# heart_capTouch.net
KiCad netlist of a schematic drawn in EAGLE
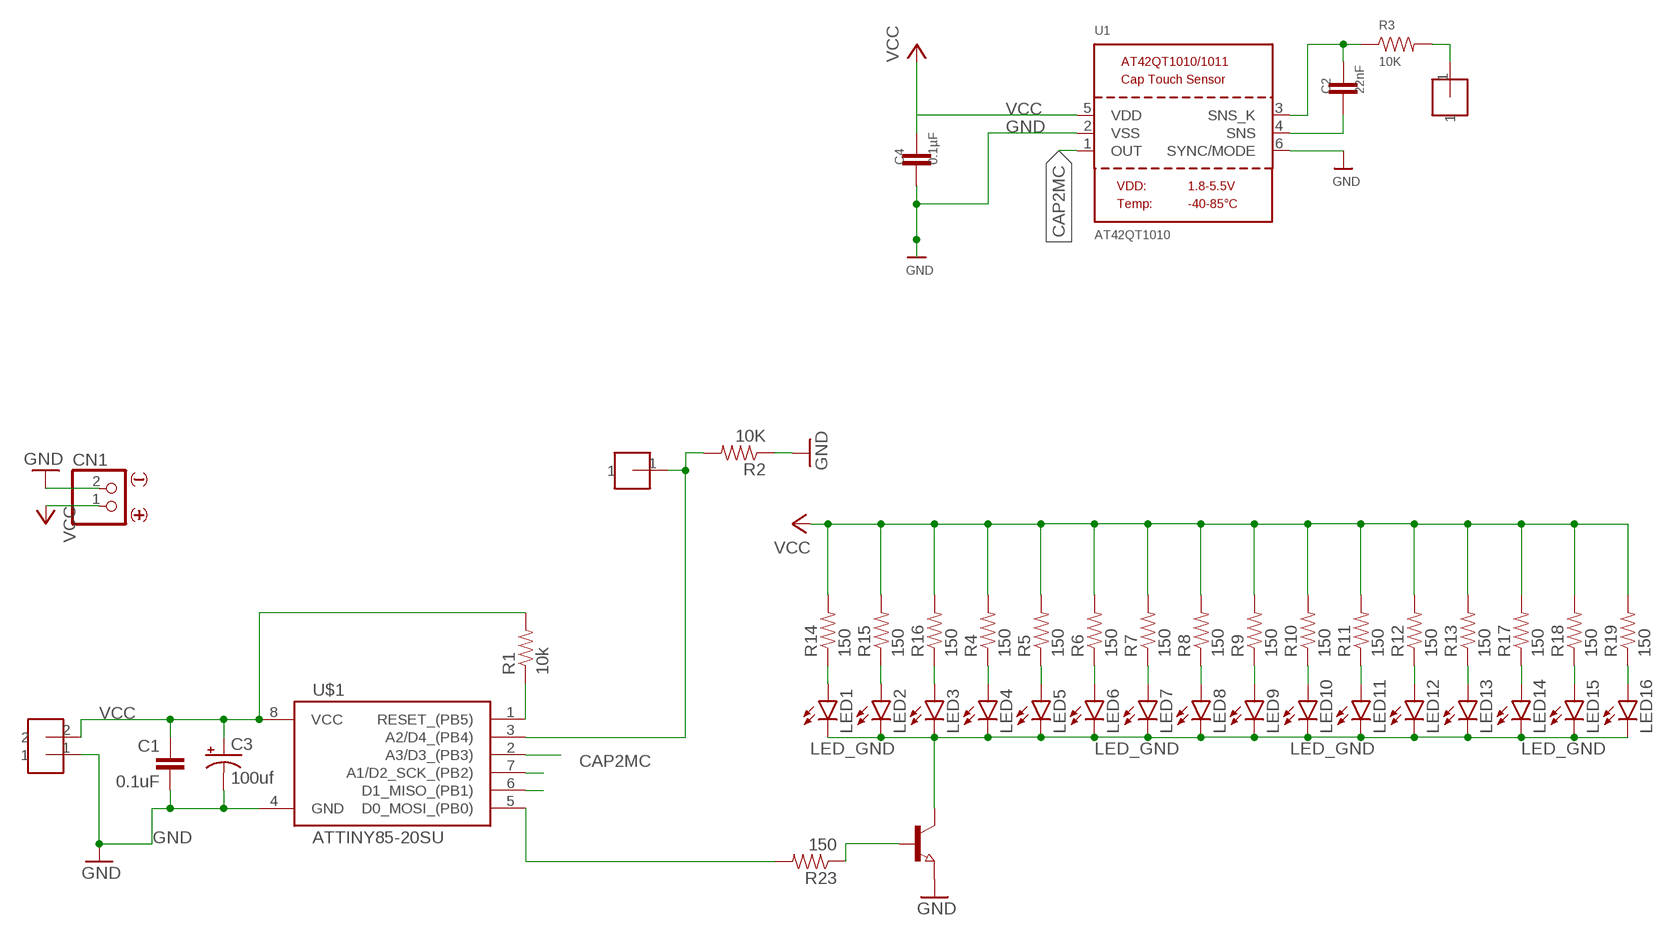
[diagram p0: schematic, sheet 1]

(export (version "E")
  (design (tool "Eeschema 10.0.6"))
  (components
    (comp (ref "C1")
      (value "0.1uF")
      (footprint "eagle-import:0805")
      (libsource (lib "eagle-import") (part "CAP-0805"))
    )
    (comp (ref "C2")
      (value "22nF")
      (footprint "eagle-import:0805")
      (libsource (lib "eagle-import") (part "CAP-0805"))
    )
    (comp (ref "C3")
      (value "100uf")
      (footprint "eagle-import:PANASONIC_D")
      (libsource (lib "eagle-import") (part "CAP_POLD"))
    )
    (comp (ref "C4")
      (value "0.1µF")
      (footprint "eagle-import:0805")
      (libsource (lib "eagle-import") (part "CAP-0805"))
    )
    (comp (ref "CN1")
      (value "JST_2PIN_BATTERY-SMT-HORIZ")
      (footprint "eagle-import:JST-PH-2-SMT-RA")
      (libsource (lib "eagle-import") (part "JST_2PIN_BATTERY-SMT-HORIZ"))
    )
    (comp (ref "LED1")
      (value "LED0603")
      (footprint "eagle-import:LED-0603")
      (libsource (lib "eagle-import") (part "LED0603"))
    )
    (comp (ref "LED2")
      (value "LED0603")
      (footprint "eagle-import:LED-0603")
      (libsource (lib "eagle-import") (part "LED0603"))
    )
    (comp (ref "LED3")
      (value "LED0603")
      (footprint "eagle-import:LED-0603")
      (libsource (lib "eagle-import") (part "LED0603"))
    )
    (comp (ref "LED4")
      (value "LED0603")
      (footprint "eagle-import:LED-0603")
      (libsource (lib "eagle-import") (part "LED0603"))
    )
    (comp (ref "LED5")
      (value "LED0603")
      (footprint "eagle-import:LED-0603")
      (libsource (lib "eagle-import") (part "LED0603"))
    )
    (comp (ref "LED6")
      (value "LED0603")
      (footprint "eagle-import:LED-0603")
      (libsource (lib "eagle-import") (part "LED0603"))
    )
    (comp (ref "LED7")
      (value "LED0603")
      (footprint "eagle-import:LED-0603")
      (libsource (lib "eagle-import") (part "LED0603"))
    )
    (comp (ref "LED8")
      (value "LED0603")
      (footprint "eagle-import:LED-0603")
      (libsource (lib "eagle-import") (part "LED0603"))
    )
    (comp (ref "LED9")
      (value "LED0603")
      (footprint "eagle-import:LED-0603")
      (libsource (lib "eagle-import") (part "LED0603"))
    )
    (comp (ref "LED10")
      (value "LED0603")
      (footprint "eagle-import:LED-0603")
      (libsource (lib "eagle-import") (part "LED0603"))
    )
    (comp (ref "LED11")
      (value "LED0603")
      (footprint "eagle-import:LED-0603")
      (libsource (lib "eagle-import") (part "LED0603"))
    )
    (comp (ref "LED12")
      (value "LED0603")
      (footprint "eagle-import:LED-0603")
      (libsource (lib "eagle-import") (part "LED0603"))
    )
    (comp (ref "LED13")
      (value "LED0603")
      (footprint "eagle-import:LED-0603")
      (libsource (lib "eagle-import") (part "LED0603"))
    )
    (comp (ref "LED14")
      (value "LED0603")
      (footprint "eagle-import:LED-0603")
      (libsource (lib "eagle-import") (part "LED0603"))
    )
    (comp (ref "LED15")
      (value "LED0603")
      (footprint "eagle-import:LED-0603")
      (libsource (lib "eagle-import") (part "LED0603"))
    )
    (comp (ref "LED16")
      (value "LED0603")
      (footprint "eagle-import:LED-0603")
      (libsource (lib "eagle-import") (part "LED0603"))
    )
    (comp (ref "Q5")
      (value "TRANSISTOR-NPN-SOT23")
      (footprint "eagle-import:SOT23")
      (libsource (lib "eagle-import") (part "TRANSISTOR-NPN-SOT23"))
    )
    (comp (ref "R1")
      (value "10k")
      (footprint "eagle-import:0805")
      (libsource (lib "eagle-import") (part "RESISTOR-0805"))
    )
    (comp (ref "R2")
      (value "10K")
      (footprint "eagle-import:0805")
      (libsource (lib "eagle-import") (part "RESISTOR-0805"))
    )
    (comp (ref "R3")
      (value "10K")
      (footprint "eagle-import:0805")
      (libsource (lib "eagle-import") (part "RESISTOR-0805"))
    )
    (comp (ref "R4")
      (value "150")
      (footprint "eagle-import:0603-RES")
      (libsource (lib "eagle-import") (part "RESISTOR0603"))
    )
    (comp (ref "R5")
      (value "150")
      (footprint "eagle-import:0603-RES")
      (libsource (lib "eagle-import") (part "RESISTOR0603"))
    )
    (comp (ref "R6")
      (value "150")
      (footprint "eagle-import:0603-RES")
      (libsource (lib "eagle-import") (part "RESISTOR0603"))
    )
    (comp (ref "R7")
      (value "150")
      (footprint "eagle-import:0603-RES")
      (libsource (lib "eagle-import") (part "RESISTOR0603"))
    )
    (comp (ref "R8")
      (value "150")
      (footprint "eagle-import:0603-RES")
      (libsource (lib "eagle-import") (part "RESISTOR0603"))
    )
    (comp (ref "R9")
      (value "150")
      (footprint "eagle-import:0603-RES")
      (libsource (lib "eagle-import") (part "RESISTOR0603"))
    )
    (comp (ref "R10")
      (value "150")
      (footprint "eagle-import:0603-RES")
      (libsource (lib "eagle-import") (part "RESISTOR0603"))
    )
    (comp (ref "R11")
      (value "150")
      (footprint "eagle-import:0603-RES")
      (libsource (lib "eagle-import") (part "RESISTOR0603"))
    )
    (comp (ref "R12")
      (value "150")
      (footprint "eagle-import:0603-RES")
      (libsource (lib "eagle-import") (part "RESISTOR0603"))
    )
    (comp (ref "R13")
      (value "150")
      (footprint "eagle-import:0603-RES")
      (libsource (lib "eagle-import") (part "RESISTOR0603"))
    )
    (comp (ref "R14")
      (value "150")
      (footprint "eagle-import:0603-RES")
      (libsource (lib "eagle-import") (part "RESISTOR0603"))
    )
    (comp (ref "R15")
      (value "150")
      (footprint "eagle-import:0603-RES")
      (libsource (lib "eagle-import") (part "RESISTOR0603"))
    )
    (comp (ref "R16")
      (value "150")
      (footprint "eagle-import:0603-RES")
      (libsource (lib "eagle-import") (part "RESISTOR0603"))
    )
    (comp (ref "R17")
      (value "150")
      (footprint "eagle-import:0603-RES")
      (libsource (lib "eagle-import") (part "RESISTOR0603"))
    )
    (comp (ref "R18")
      (value "150")
      (footprint "eagle-import:0603-RES")
      (libsource (lib "eagle-import") (part "RESISTOR0603"))
    )
    (comp (ref "R19")
      (value "150")
      (footprint "eagle-import:0603-RES")
      (libsource (lib "eagle-import") (part "RESISTOR0603"))
    )
    (comp (ref "R23")
      (value "150")
      (footprint "eagle-import:0805")
      (libsource (lib "eagle-import") (part "RESISTOR-0805"))
    )
    (comp (ref "U$1")
      (value "ATTINY85-20SU")
      (footprint "eagle-import:SOIC8")
      (libsource (lib "eagle-import") (part "ATTINY85-20SU"))
    )
    (comp (ref "U$2")
      (value "HEADER-2-TESTPOINT")
      (footprint "eagle-import:TESTPOINT-2")
      (libsource (lib "eagle-import") (part "HEADER-2-TESTPOINT"))
    )
    (comp (ref "U$4")
      (value "HEADER-1-TESTPOINT")
      (footprint "eagle-import:TESTPOINT-1")
      (libsource (lib "eagle-import") (part "HEADER-1-TESTPOINT"))
    )
    (comp (ref "U$6")
      (value "HEADER-1-TESTPOINT")
      (footprint "eagle-import:TESTPOINT-1")
      (libsource (lib "eagle-import") (part "HEADER-1-TESTPOINT"))
    )
    (comp (ref "U1")
      (value "AT42QT1010")
      (footprint "eagle-import:SOT23-6")
      (libsource (lib "eagle-import") (part "AT42QT1010/1"))
    )
  )
  (nets
    (net (code "1") (name "/LED_GND") (class "Default")
      (node (ref "LED1") (pin "C") (pinfunction "C_C") (pintype "passive"))
      (node (ref "LED10") (pin "C") (pinfunction "C_C") (pintype "passive"))
      (node (ref "LED11") (pin "C") (pinfunction "C_C") (pintype "passive"))
      (node (ref "LED12") (pin "C") (pinfunction "C_C") (pintype "passive"))
      (node (ref "LED13") (pin "C") (pinfunction "C_C") (pintype "passive"))
      (node (ref "LED14") (pin "C") (pinfunction "C_C") (pintype "passive"))
      (node (ref "LED15") (pin "C") (pinfunction "C_C") (pintype "passive"))
      (node (ref "LED16") (pin "C") (pinfunction "C_C") (pintype "passive"))
      (node (ref "LED2") (pin "C") (pinfunction "C_C") (pintype "passive"))
      (node (ref "LED3") (pin "C") (pinfunction "C_C") (pintype "passive"))
      (node (ref "LED4") (pin "C") (pinfunction "C_C") (pintype "passive"))
      (node (ref "LED5") (pin "C") (pinfunction "C_C") (pintype "passive"))
      (node (ref "LED6") (pin "C") (pinfunction "C_C") (pintype "passive"))
      (node (ref "LED7") (pin "C") (pinfunction "C_C") (pintype "passive"))
      (node (ref "LED8") (pin "C") (pinfunction "C_C") (pintype "passive"))
      (node (ref "LED9") (pin "C") (pinfunction "C_C") (pintype "passive"))
      (node (ref "Q5") (pin "3") (pinfunction "C_3") (pintype "passive"))
    )
    (net (code "2") (name "CAP2MC") (class "Default")
      (node (ref "U$1") (pin "2") (pinfunction "A3/D3_(PB3)_2") (pintype "bidirectional"))
      (node (ref "U1") (pin "1") (pinfunction "OUT_1") (pintype "output"))
    )
    (net (code "3") (name "GND") (class "Default")
      (node (ref "C1") (pin "2") (pinfunction "2_2") (pintype "passive"))
      (node (ref "C3") (pin "-") (pinfunction "-_-") (pintype "passive"))
      (node (ref "C4") (pin "2") (pinfunction "2_2") (pintype "passive"))
      (node (ref "CN1") (pin "2") (pinfunction "1_2") (pintype "passive"))
      (node (ref "Q5") (pin "2") (pinfunction "E_2") (pintype "passive"))
      (node (ref "R2") (pin "1") (pinfunction "1_1") (pintype "passive"))
      (node (ref "U$1") (pin "4") (pinfunction "GND_4") (pintype "power_in"))
      (node (ref "U$2") (pin "1") (pinfunction "1_1") (pintype "bidirectional"))
      (node (ref "U1") (pin "2") (pinfunction "VSS_2") (pintype "power_in"))
      (node (ref "U1") (pin "6") (pinfunction "SYNC/MODE_6") (pintype "input"))
    )
    (net (code "4") (name "Net-(LED1-PadA)") (class "Default")
      (node (ref "LED1") (pin "A") (pinfunction "A_A") (pintype "passive"))
      (node (ref "R14") (pin "1") (pinfunction "1_1") (pintype "passive"))
    )
    (net (code "5") (name "Net-(LED2-PadA)") (class "Default")
      (node (ref "LED2") (pin "A") (pinfunction "A_A") (pintype "passive"))
      (node (ref "R15") (pin "1") (pinfunction "1_1") (pintype "passive"))
    )
    (net (code "6") (name "Net-(LED3-PadA)") (class "Default")
      (node (ref "LED3") (pin "A") (pinfunction "A_A") (pintype "passive"))
      (node (ref "R16") (pin "1") (pinfunction "1_1") (pintype "passive"))
    )
    (net (code "7") (name "Net-(LED4-PadA)") (class "Default")
      (node (ref "LED4") (pin "A") (pinfunction "A_A") (pintype "passive"))
      (node (ref "R4") (pin "1") (pinfunction "1_1") (pintype "passive"))
    )
    (net (code "8") (name "Net-(LED5-PadA)") (class "Default")
      (node (ref "LED5") (pin "A") (pinfunction "A_A") (pintype "passive"))
      (node (ref "R5") (pin "1") (pinfunction "1_1") (pintype "passive"))
    )
    (net (code "9") (name "Net-(LED6-PadA)") (class "Default")
      (node (ref "LED6") (pin "A") (pinfunction "A_A") (pintype "passive"))
      (node (ref "R6") (pin "1") (pinfunction "1_1") (pintype "passive"))
    )
    (net (code "10") (name "Net-(LED7-PadA)") (class "Default")
      (node (ref "LED7") (pin "A") (pinfunction "A_A") (pintype "passive"))
      (node (ref "R7") (pin "1") (pinfunction "1_1") (pintype "passive"))
    )
    (net (code "11") (name "Net-(LED8-PadA)") (class "Default")
      (node (ref "LED8") (pin "A") (pinfunction "A_A") (pintype "passive"))
      (node (ref "R8") (pin "1") (pinfunction "1_1") (pintype "passive"))
    )
    (net (code "12") (name "Net-(LED9-PadA)") (class "Default")
      (node (ref "LED9") (pin "A") (pinfunction "A_A") (pintype "passive"))
      (node (ref "R9") (pin "1") (pinfunction "1_1") (pintype "passive"))
    )
    (net (code "13") (name "Net-(LED10-PadA)") (class "Default")
      (node (ref "LED10") (pin "A") (pinfunction "A_A") (pintype "passive"))
      (node (ref "R10") (pin "1") (pinfunction "1_1") (pintype "passive"))
    )
    (net (code "14") (name "Net-(LED11-PadA)") (class "Default")
      (node (ref "LED11") (pin "A") (pinfunction "A_A") (pintype "passive"))
      (node (ref "R11") (pin "1") (pinfunction "1_1") (pintype "passive"))
    )
    (net (code "15") (name "Net-(LED12-PadA)") (class "Default")
      (node (ref "LED12") (pin "A") (pinfunction "A_A") (pintype "passive"))
      (node (ref "R12") (pin "1") (pinfunction "1_1") (pintype "passive"))
    )
    (net (code "16") (name "Net-(LED13-PadA)") (class "Default")
      (node (ref "LED13") (pin "A") (pinfunction "A_A") (pintype "passive"))
      (node (ref "R13") (pin "1") (pinfunction "1_1") (pintype "passive"))
    )
    (net (code "17") (name "Net-(LED14-PadA)") (class "Default")
      (node (ref "LED14") (pin "A") (pinfunction "A_A") (pintype "passive"))
      (node (ref "R17") (pin "1") (pinfunction "1_1") (pintype "passive"))
    )
    (net (code "18") (name "Net-(LED15-PadA)") (class "Default")
      (node (ref "LED15") (pin "A") (pinfunction "A_A") (pintype "passive"))
      (node (ref "R18") (pin "1") (pinfunction "1_1") (pintype "passive"))
    )
    (net (code "19") (name "Net-(LED16-PadA)") (class "Default")
      (node (ref "LED16") (pin "A") (pinfunction "A_A") (pintype "passive"))
      (node (ref "R19") (pin "1") (pinfunction "1_1") (pintype "passive"))
    )
    (net (code "20") (name "Net-(Q5-B)") (class "Default")
      (node (ref "Q5") (pin "1") (pinfunction "B_1") (pintype "passive"))
      (node (ref "R23") (pin "1") (pinfunction "1_1") (pintype "passive"))
    )
    (net (code "21") (name "Net-(R3-Pad2)") (class "Default")
      (node (ref "R3") (pin "2") (pinfunction "2_2") (pintype "passive"))
      (node (ref "U$6") (pin "1") (pinfunction "1_1") (pintype "bidirectional"))
    )
    (net (code "22") (name "Net-(U$1-A2{slash}D4_(PB4))") (class "Default")
      (node (ref "R2") (pin "2") (pinfunction "2_2") (pintype "passive"))
      (node (ref "U$1") (pin "3") (pinfunction "A2/D4_(PB4)_3") (pintype "bidirectional"))
      (node (ref "U$4") (pin "1") (pinfunction "1_1") (pintype "bidirectional"))
    )
    (net (code "23") (name "Net-(U$1-D0_MOSI_(PB0))") (class "Default")
      (node (ref "R23") (pin "2") (pinfunction "2_2") (pintype "passive"))
      (node (ref "U$1") (pin "5") (pinfunction "D0_MOSI_(PB0)_5") (pintype "bidirectional"))
    )
    (net (code "24") (name "Net-(U$1-RESET_(PB5))") (class "Default")
      (node (ref "R1") (pin "1") (pinfunction "1_1") (pintype "passive"))
      (node (ref "U$1") (pin "1") (pinfunction "RESET_(PB5)_1") (pintype "bidirectional"))
    )
    (net (code "25") (name "Net-(U1-SNS)") (class "Default")
      (node (ref "C2") (pin "2") (pinfunction "2_2") (pintype "passive"))
      (node (ref "U1") (pin "4") (pinfunction "SNS_4") (pintype "bidirectional"))
    )
    (net (code "26") (name "Net-(U1-SNS_K)") (class "Default")
      (node (ref "C2") (pin "1") (pinfunction "1_1") (pintype "passive"))
      (node (ref "R3") (pin "1") (pinfunction "1_1") (pintype "passive"))
      (node (ref "U1") (pin "3") (pinfunction "SNS_K_3") (pintype "bidirectional"))
    )
    (net (code "27") (name "VCC") (class "Default")
      (node (ref "C1") (pin "1") (pinfunction "1_1") (pintype "passive"))
      (node (ref "C3") (pin "+") (pinfunction "+_+") (pintype "passive"))
      (node (ref "C4") (pin "1") (pinfunction "1_1") (pintype "passive"))
      (node (ref "CN1") (pin "1") (pinfunction "2_1") (pintype "passive"))
      (node (ref "R1") (pin "2") (pinfunction "2_2") (pintype "passive"))
      (node (ref "R10") (pin "2") (pinfunction "2_2") (pintype "passive"))
      (node (ref "R11") (pin "2") (pinfunction "2_2") (pintype "passive"))
      (node (ref "R12") (pin "2") (pinfunction "2_2") (pintype "passive"))
      (node (ref "R13") (pin "2") (pinfunction "2_2") (pintype "passive"))
      (node (ref "R14") (pin "2") (pinfunction "2_2") (pintype "passive"))
      (node (ref "R15") (pin "2") (pinfunction "2_2") (pintype "passive"))
      (node (ref "R16") (pin "2") (pinfunction "2_2") (pintype "passive"))
      (node (ref "R17") (pin "2") (pinfunction "2_2") (pintype "passive"))
      (node (ref "R18") (pin "2") (pinfunction "2_2") (pintype "passive"))
      (node (ref "R19") (pin "2") (pinfunction "2_2") (pintype "passive"))
      (node (ref "R4") (pin "2") (pinfunction "2_2") (pintype "passive"))
      (node (ref "R5") (pin "2") (pinfunction "2_2") (pintype "passive"))
      (node (ref "R6") (pin "2") (pinfunction "2_2") (pintype "passive"))
      (node (ref "R7") (pin "2") (pinfunction "2_2") (pintype "passive"))
      (node (ref "R8") (pin "2") (pinfunction "2_2") (pintype "passive"))
      (node (ref "R9") (pin "2") (pinfunction "2_2") (pintype "passive"))
      (node (ref "U$1") (pin "8") (pinfunction "VCC_8") (pintype "power_in"))
      (node (ref "U$2") (pin "2") (pinfunction "2_2") (pintype "bidirectional"))
      (node (ref "U1") (pin "5") (pinfunction "VDD_5") (pintype "power_in"))
    )
    (net (code "28") (name "unconnected-(U$1-A1{slash}D2_SCK_(PB2)-Pad7)") (class "Default")
      (node (ref "U$1") (pin "7") (pinfunction "A1/D2_SCK_(PB2)_7") (pintype "bidirectional"))
    )
    (net (code "29") (name "unconnected-(U$1-D1_MISO_(PB1)-Pad6)") (class "Default")
      (node (ref "U$1") (pin "6") (pinfunction "D1_MISO_(PB1)_6") (pintype "bidirectional"))
    )
  )
)
